# LS7366Rshield101.net
KiCad netlist of a schematic drawn in EAGLE
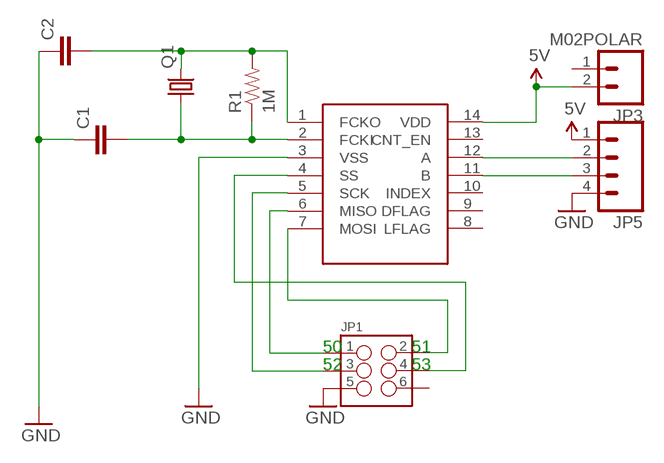
[diagram p0: schematic, sheet 1]

(export (version "E")
  (design (tool "Eeschema 10.0.6"))
  (components
    (comp (ref "C1")
      (value "0.1UF-50V-20%(PTH)KIT-EZ")
      (footprint "eagle-import:CAP-PTH-SMALL-KIT")
      (libsource (lib "eagle-import") (part "0.1UF-50V-20%(PTH)KIT-EZ"))
    )
    (comp (ref "C2")
      (value "0.1UF-50V-20%(PTH)KIT-EZ")
      (footprint "eagle-import:CAP-PTH-SMALL-KIT")
      (libsource (lib "eagle-import") (part "0.1UF-50V-20%(PTH)KIT-EZ"))
    )
    (comp (ref "JP1")
      (value "M03X2POGO_PINS")
      (footprint "eagle-import:2X3_POGO")
      (libsource (lib "eagle-import") (part "M03X2POGO_PINS"))
    )
    (comp (ref "JP3")
      (value "M02POLAR")
      (footprint "eagle-import:MOLEX-1X2")
      (libsource (lib "eagle-import") (part "M02POLAR"))
    )
    (comp (ref "JP5")
      (value "M04POLAR")
      (footprint "eagle-import:MOLEX-1X4")
      (libsource (lib "eagle-import") (part "M04POLAR"))
    )
    (comp (ref "LS7366R")
      (value "LS7366R")
      (footprint "eagle-import:SO014")
      (libsource (lib "eagle-import") (part "LS7366R"))
    )
    (comp (ref "Q1")
      (value "CRYSTALHC49S")
      (footprint "eagle-import:HC49_S")
      (libsource (lib "eagle-import") (part "CRYSTALHC49S"))
    )
    (comp (ref "R1")
      (value "1M")
      (footprint "eagle-import:AXIAL-0.3")
      (libsource (lib "eagle-import") (part "1KOHM-1/4W-1%(PTH)"))
    )
  )
  (nets
    (net (code "1") (name "5V") (class "Default")
      (node (ref "JP3") (pin "2") (pinfunction "2_2") (pintype "passive"))
      (node (ref "JP5") (pin "1") (pinfunction "1_1") (pintype "passive"))
      (node (ref "LS7366R") (pin "14") (pinfunction "VDD_14") (pintype "bidirectional"))
    )
    (net (code "2") (name "GND") (class "Default")
      (node (ref "C1") (pin "1") (pinfunction "1_1") (pintype "passive"))
      (node (ref "C2") (pin "1") (pinfunction "1_1") (pintype "passive"))
      (node (ref "JP1") (pin "P$5") (pinfunction "5_P$5") (pintype "bidirectional"))
      (node (ref "JP5") (pin "4") (pinfunction "4_4") (pintype "passive"))
      (node (ref "LS7366R") (pin "3") (pinfunction "VSS_3") (pintype "bidirectional"))
    )
    (net (code "3") (name "Net-(JP1-1)") (class "Default")
      (node (ref "JP1") (pin "P$1") (pinfunction "1_P$1") (pintype "bidirectional"))
      (node (ref "LS7366R") (pin "6") (pinfunction "MISO_6") (pintype "bidirectional"))
    )
    (net (code "4") (name "Net-(JP1-2)") (class "Default")
      (node (ref "JP1") (pin "P$2") (pinfunction "2_P$2") (pintype "bidirectional"))
      (node (ref "LS7366R") (pin "7") (pinfunction "MOSI_7") (pintype "bidirectional"))
    )
    (net (code "5") (name "Net-(JP1-3)") (class "Default")
      (node (ref "JP1") (pin "P$3") (pinfunction "3_P$3") (pintype "bidirectional"))
      (node (ref "LS7366R") (pin "5") (pinfunction "SCK_5") (pintype "bidirectional"))
    )
    (net (code "6") (name "Net-(JP1-4)") (class "Default")
      (node (ref "JP1") (pin "P$4") (pinfunction "4_P$4") (pintype "bidirectional"))
      (node (ref "LS7366R") (pin "4") (pinfunction "SS_4") (pintype "bidirectional"))
    )
    (net (code "7") (name "Net-(LS7366R-A)") (class "Default")
      (node (ref "JP5") (pin "2") (pinfunction "2_2") (pintype "passive"))
      (node (ref "LS7366R") (pin "12") (pinfunction "A_12") (pintype "bidirectional"))
    )
    (net (code "8") (name "Net-(LS7366R-B)") (class "Default")
      (node (ref "JP5") (pin "3") (pinfunction "3_3") (pintype "passive"))
      (node (ref "LS7366R") (pin "11") (pinfunction "B_11") (pintype "bidirectional"))
    )
    (net (code "9") (name "Net-(LS7366R-FCKI)") (class "Default")
      (node (ref "C1") (pin "2") (pinfunction "2_2") (pintype "passive"))
      (node (ref "LS7366R") (pin "2") (pinfunction "FCKI_2") (pintype "bidirectional"))
      (node (ref "Q1") (pin "1") (pinfunction "1_1") (pintype "passive"))
      (node (ref "R1") (pin "P$1") (pinfunction "1_P$1") (pintype "passive"))
    )
    (net (code "10") (name "Net-(LS7366R-FCKO)") (class "Default")
      (node (ref "C2") (pin "2") (pinfunction "2_2") (pintype "passive"))
      (node (ref "LS7366R") (pin "1") (pinfunction "FCKO_1") (pintype "bidirectional"))
      (node (ref "Q1") (pin "2") (pinfunction "2_2") (pintype "passive"))
      (node (ref "R1") (pin "P$2") (pinfunction "2_P$2") (pintype "passive"))
    )
    (net (code "11") (name "unconnected-(JP1-6-PadP$6)") (class "Default")
      (node (ref "JP1") (pin "P$6") (pinfunction "6_P$6") (pintype "bidirectional"))
    )
    (net (code "12") (name "unconnected-(JP3-Pad1)") (class "Default")
      (node (ref "JP3") (pin "1") (pinfunction "1_1") (pintype "passive"))
    )
    (net (code "13") (name "unconnected-(LS7366R-CNT_EN-Pad13)") (class "Default")
      (node (ref "LS7366R") (pin "13") (pinfunction "CNT_EN_13") (pintype "bidirectional"))
    )
    (net (code "14") (name "unconnected-(LS7366R-DFLAG-Pad9)") (class "Default")
      (node (ref "LS7366R") (pin "9") (pinfunction "DFLAG_9") (pintype "bidirectional"))
    )
    (net (code "15") (name "unconnected-(LS7366R-INDEX-Pad10)") (class "Default")
      (node (ref "LS7366R") (pin "10") (pinfunction "INDEX_10") (pintype "bidirectional"))
    )
    (net (code "16") (name "unconnected-(LS7366R-LFLAG-Pad8)") (class "Default")
      (node (ref "LS7366R") (pin "8") (pinfunction "LFLAG_8") (pintype "bidirectional"))
    )
  )
)
